# CPU_Power.net
KiCad netlist of a schematic drawn in Altium Designer
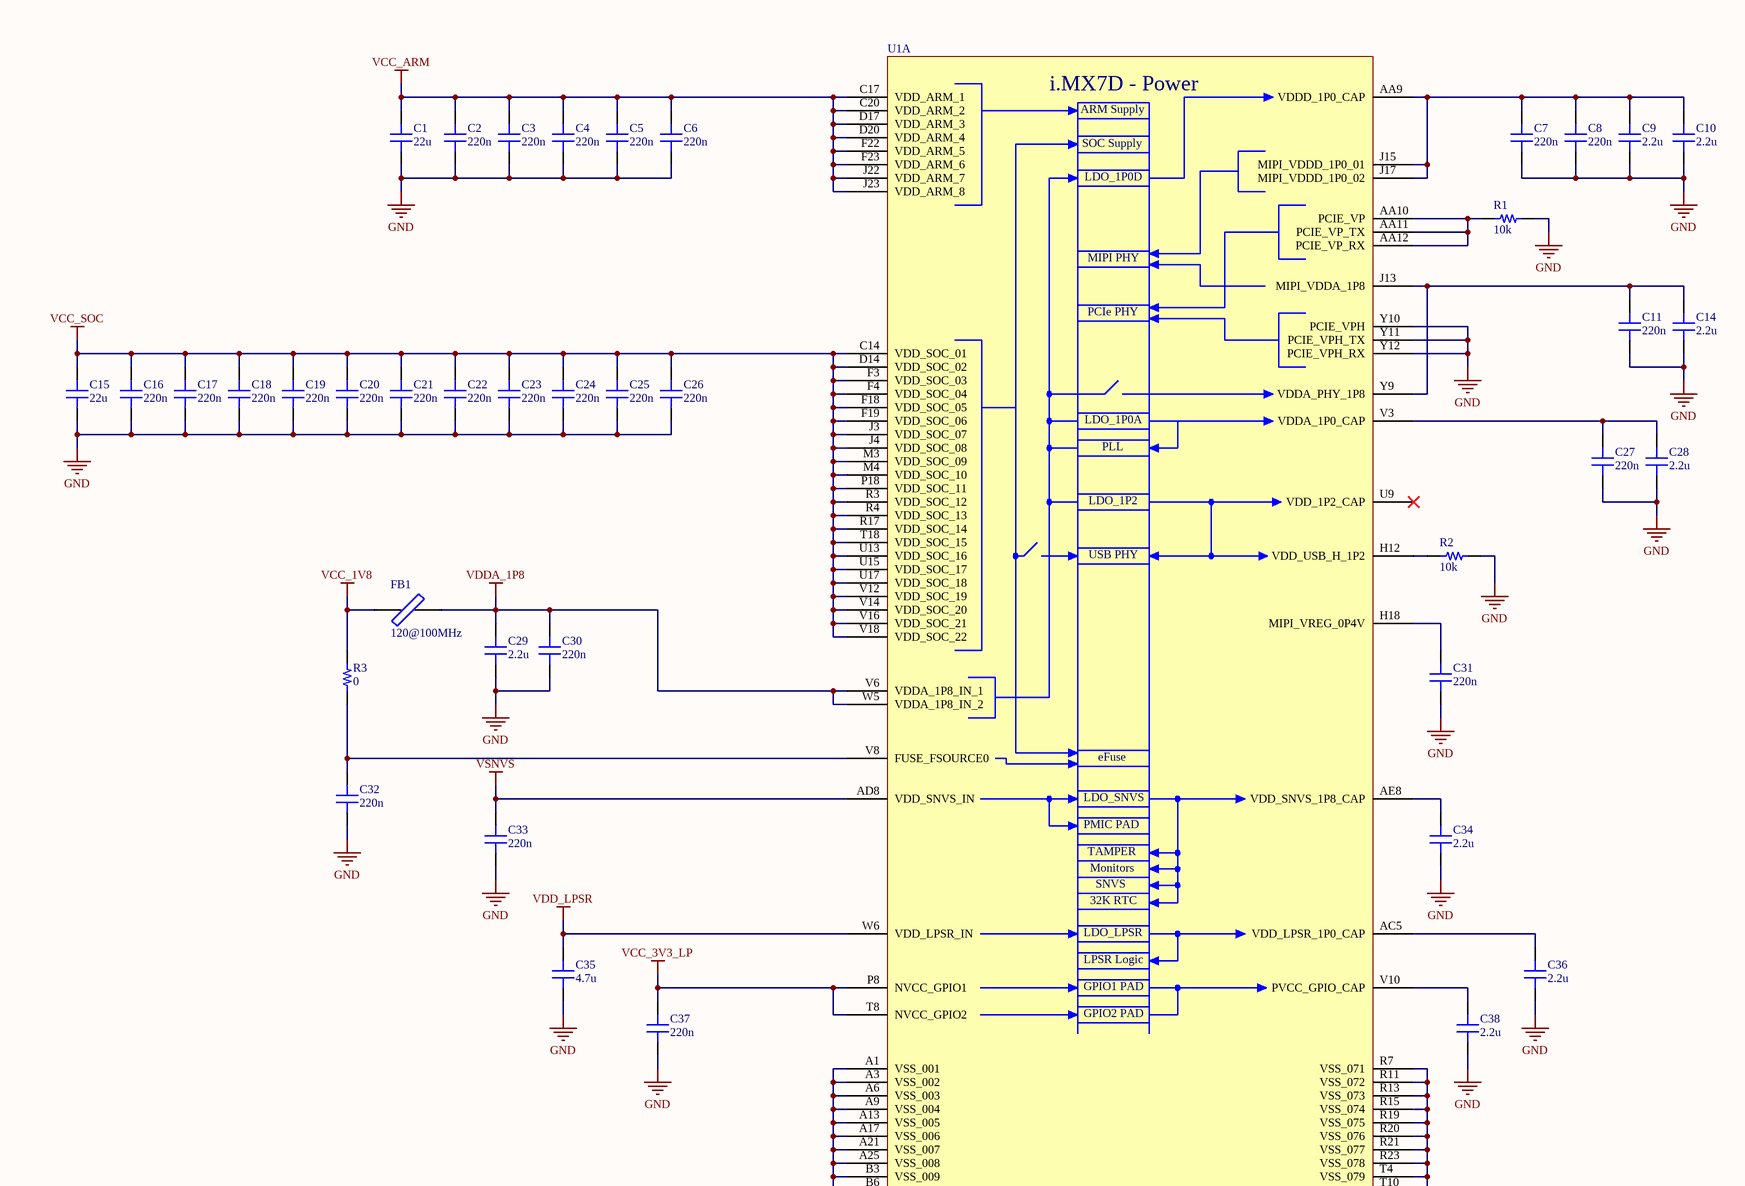
[diagram p0: CPU Power.SchDoc, top left]
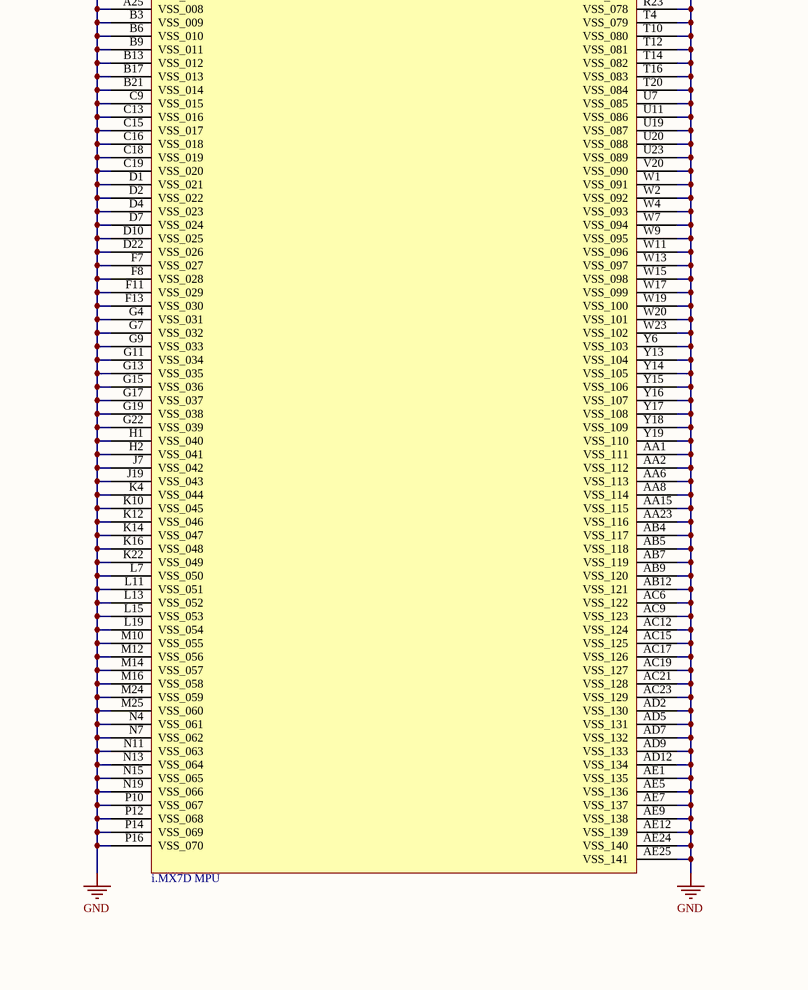
[diagram p1: CPU Power.SchDoc, bottom left]
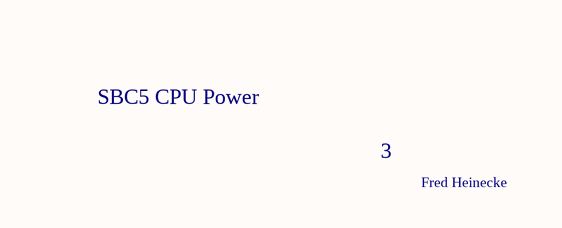
[diagram p2: CPU Power.SchDoc, bottom right]

(export (version "E")
  (design (tool "Eeschema 10.0.6"))
  (components
    (comp (ref "C1")
      (value "22u")
      (footprint "C0603")
      (description "0603 22 uF 10 V ±20% Tolerance X5R Multilayer Ceramic Chip Capacitor")
      (fields
        (field (name "MANUFACTURER") "Murata")
        (field (name "MANUFACTURER PART NUMBER") "GRM188R61A226ME15D")
      )
      (libsource (lib "SBC5") (part "GRM188R61A226ME15D"))
    )
    (comp (ref "C2")
      (value "220n")
      (footprint "C0201")
      (description "Cap Ceramic Monolithic 0.22uF 16VDC 10% SMD Paper T/R")
      (fields
        (field (name "MANUFACTURER") "Murata")
        (field (name "MANUFACTURER PART NUMBER") "GRM033R61C224KE14D")
      )
      (libsource (lib "SBC5") (part "GRM033R61C224KE14D"))
    )
    (comp (ref "C3")
      (value "220n")
      (footprint "C0201")
      (description "Cap Ceramic Monolithic 0.22uF 16VDC 10% SMD Paper T/R")
      (fields
        (field (name "MANUFACTURER") "Murata")
        (field (name "MANUFACTURER PART NUMBER") "GRM033R61C224KE14D")
      )
      (libsource (lib "SBC5") (part "GRM033R61C224KE14D"))
    )
    (comp (ref "C4")
      (value "220n")
      (footprint "C0201")
      (description "Cap Ceramic Monolithic 0.22uF 16VDC 10% SMD Paper T/R")
      (fields
        (field (name "MANUFACTURER") "Murata")
        (field (name "MANUFACTURER PART NUMBER") "GRM033R61C224KE14D")
      )
      (libsource (lib "SBC5") (part "GRM033R61C224KE14D"))
    )
    (comp (ref "C5")
      (value "220n")
      (footprint "C0201")
      (description "Cap Ceramic Monolithic 0.22uF 16VDC 10% SMD Paper T/R")
      (fields
        (field (name "MANUFACTURER") "Murata")
        (field (name "MANUFACTURER PART NUMBER") "GRM033R61C224KE14D")
      )
      (libsource (lib "SBC5") (part "GRM033R61C224KE14D"))
    )
    (comp (ref "C6")
      (value "220n")
      (footprint "C0201")
      (description "Cap Ceramic Monolithic 0.22uF 16VDC 10% SMD Paper T/R")
      (fields
        (field (name "MANUFACTURER") "Murata")
        (field (name "MANUFACTURER PART NUMBER") "GRM033R61C224KE14D")
      )
      (libsource (lib "SBC5") (part "GRM033R61C224KE14D"))
    )
    (comp (ref "C7")
      (value "220n")
      (footprint "C0201")
      (description "Cap Ceramic Monolithic 0.22uF 16VDC 10% SMD Paper T/R")
      (fields
        (field (name "MANUFACTURER") "Murata")
        (field (name "MANUFACTURER PART NUMBER") "GRM033R61C224KE14D")
      )
      (libsource (lib "SBC5") (part "GRM033R61C224KE14D"))
    )
    (comp (ref "C8")
      (value "220n")
      (footprint "C0201")
      (description "Cap Ceramic Monolithic 0.22uF 16VDC 10% SMD Paper T/R")
      (fields
        (field (name "MANUFACTURER") "Murata")
        (field (name "MANUFACTURER PART NUMBER") "GRM033R61C224KE14D")
      )
      (libsource (lib "SBC5") (part "GRM033R61C224KE14D"))
    )
    (comp (ref "C9")
      (value "2.2u")
      (footprint "C0402")
      (description "TAIYO YUDEN         LMK105BJ225MV-F            CERAMIC CAPACITOR, 2.2UF, 10V, X5R, 20%, 0402")
      (fields
        (field (name "MANUFACTURER") "Taiyo Yuden")
        (field (name "MANUFACTURER PART NUMBER") "LMK105BJ225MV-F")
      )
      (libsource (lib "SBC5") (part "LMK105BJ225MV-F"))
    )
    (comp (ref "C10")
      (value "2.2u")
      (footprint "C0402")
      (description "TAIYO YUDEN         LMK105BJ225MV-F            CERAMIC CAPACITOR, 2.2UF, 10V, X5R, 20%, 0402")
      (fields
        (field (name "MANUFACTURER") "Taiyo Yuden")
        (field (name "MANUFACTURER PART NUMBER") "LMK105BJ225MV-F")
      )
      (libsource (lib "SBC5") (part "LMK105BJ225MV-F"))
    )
    (comp (ref "C11")
      (value "220n")
      (footprint "C0201")
      (description "Cap Ceramic Monolithic 0.22uF 16VDC 10% SMD Paper T/R")
      (fields
        (field (name "MANUFACTURER") "Murata")
        (field (name "MANUFACTURER PART NUMBER") "GRM033R61C224KE14D")
      )
      (libsource (lib "SBC5") (part "GRM033R61C224KE14D"))
    )
    (comp (ref "C14")
      (value "2.2u")
      (footprint "C0402")
      (description "TAIYO YUDEN         LMK105BJ225MV-F            CERAMIC CAPACITOR, 2.2UF, 10V, X5R, 20%, 0402")
      (fields
        (field (name "MANUFACTURER") "Taiyo Yuden")
        (field (name "MANUFACTURER PART NUMBER") "LMK105BJ225MV-F")
      )
      (libsource (lib "SBC5") (part "LMK105BJ225MV-F"))
    )
    (comp (ref "C15")
      (value "22u")
      (footprint "C0603")
      (description "0603 22 uF 10 V ±20% Tolerance X5R Multilayer Ceramic Chip Capacitor")
      (fields
        (field (name "MANUFACTURER") "Murata")
        (field (name "MANUFACTURER PART NUMBER") "GRM188R61A226ME15D")
      )
      (libsource (lib "SBC5") (part "GRM188R61A226ME15D"))
    )
    (comp (ref "C16")
      (value "220n")
      (footprint "C0201")
      (description "Cap Ceramic Monolithic 0.22uF 16VDC 10% SMD Paper T/R")
      (fields
        (field (name "MANUFACTURER") "Murata")
        (field (name "MANUFACTURER PART NUMBER") "GRM033R61C224KE14D")
      )
      (libsource (lib "SBC5") (part "GRM033R61C224KE14D"))
    )
    (comp (ref "C17")
      (value "220n")
      (footprint "C0201")
      (description "Cap Ceramic Monolithic 0.22uF 16VDC 10% SMD Paper T/R")
      (fields
        (field (name "MANUFACTURER") "Murata")
        (field (name "MANUFACTURER PART NUMBER") "GRM033R61C224KE14D")
      )
      (libsource (lib "SBC5") (part "GRM033R61C224KE14D"))
    )
    (comp (ref "C18")
      (value "220n")
      (footprint "C0201")
      (description "Cap Ceramic Monolithic 0.22uF 16VDC 10% SMD Paper T/R")
      (fields
        (field (name "MANUFACTURER") "Murata")
        (field (name "MANUFACTURER PART NUMBER") "GRM033R61C224KE14D")
      )
      (libsource (lib "SBC5") (part "GRM033R61C224KE14D"))
    )
    (comp (ref "C19")
      (value "220n")
      (footprint "C0201")
      (description "Cap Ceramic Monolithic 0.22uF 16VDC 10% SMD Paper T/R")
      (fields
        (field (name "MANUFACTURER") "Murata")
        (field (name "MANUFACTURER PART NUMBER") "GRM033R61C224KE14D")
      )
      (libsource (lib "SBC5") (part "GRM033R61C224KE14D"))
    )
    (comp (ref "C20")
      (value "220n")
      (footprint "C0201")
      (description "Cap Ceramic Monolithic 0.22uF 16VDC 10% SMD Paper T/R")
      (fields
        (field (name "MANUFACTURER") "Murata")
        (field (name "MANUFACTURER PART NUMBER") "GRM033R61C224KE14D")
      )
      (libsource (lib "SBC5") (part "GRM033R61C224KE14D"))
    )
    (comp (ref "C21")
      (value "220n")
      (footprint "C0201")
      (description "Cap Ceramic Monolithic 0.22uF 16VDC 10% SMD Paper T/R")
      (fields
        (field (name "MANUFACTURER") "Murata")
        (field (name "MANUFACTURER PART NUMBER") "GRM033R61C224KE14D")
      )
      (libsource (lib "SBC5") (part "GRM033R61C224KE14D"))
    )
    (comp (ref "C22")
      (value "220n")
      (footprint "C0201")
      (description "Cap Ceramic Monolithic 0.22uF 16VDC 10% SMD Paper T/R")
      (fields
        (field (name "MANUFACTURER") "Murata")
        (field (name "MANUFACTURER PART NUMBER") "GRM033R61C224KE14D")
      )
      (libsource (lib "SBC5") (part "GRM033R61C224KE14D"))
    )
    (comp (ref "C23")
      (value "220n")
      (footprint "C0201")
      (description "Cap Ceramic Monolithic 0.22uF 16VDC 10% SMD Paper T/R")
      (fields
        (field (name "MANUFACTURER") "Murata")
        (field (name "MANUFACTURER PART NUMBER") "GRM033R61C224KE14D")
      )
      (libsource (lib "SBC5") (part "GRM033R61C224KE14D"))
    )
    (comp (ref "C24")
      (value "220n")
      (footprint "C0201")
      (description "Cap Ceramic Monolithic 0.22uF 16VDC 10% SMD Paper T/R")
      (fields
        (field (name "MANUFACTURER") "Murata")
        (field (name "MANUFACTURER PART NUMBER") "GRM033R61C224KE14D")
      )
      (libsource (lib "SBC5") (part "GRM033R61C224KE14D"))
    )
    (comp (ref "C25")
      (value "220n")
      (footprint "C0201")
      (description "Cap Ceramic Monolithic 0.22uF 16VDC 10% SMD Paper T/R")
      (fields
        (field (name "MANUFACTURER") "Murata")
        (field (name "MANUFACTURER PART NUMBER") "GRM033R61C224KE14D")
      )
      (libsource (lib "SBC5") (part "GRM033R61C224KE14D"))
    )
    (comp (ref "C26")
      (value "220n")
      (footprint "C0201")
      (description "Cap Ceramic Monolithic 0.22uF 16VDC 10% SMD Paper T/R")
      (fields
        (field (name "MANUFACTURER") "Murata")
        (field (name "MANUFACTURER PART NUMBER") "GRM033R61C224KE14D")
      )
      (libsource (lib "SBC5") (part "GRM033R61C224KE14D"))
    )
    (comp (ref "C27")
      (value "220n")
      (footprint "C0201")
      (description "Cap Ceramic Monolithic 0.22uF 16VDC 10% SMD Paper T/R")
      (fields
        (field (name "MANUFACTURER") "Murata")
        (field (name "MANUFACTURER PART NUMBER") "GRM033R61C224KE14D")
      )
      (libsource (lib "SBC5") (part "GRM033R61C224KE14D"))
    )
    (comp (ref "C28")
      (value "2.2u")
      (footprint "C0402")
      (description "TAIYO YUDEN         LMK105BJ225MV-F            CERAMIC CAPACITOR, 2.2UF, 10V, X5R, 20%, 0402")
      (fields
        (field (name "MANUFACTURER") "Taiyo Yuden")
        (field (name "MANUFACTURER PART NUMBER") "LMK105BJ225MV-F")
      )
      (libsource (lib "SBC5") (part "LMK105BJ225MV-F"))
    )
    (comp (ref "C29")
      (value "2.2u")
      (footprint "C0402")
      (description "TAIYO YUDEN         LMK105BJ225MV-F            CERAMIC CAPACITOR, 2.2UF, 10V, X5R, 20%, 0402")
      (fields
        (field (name "MANUFACTURER") "Taiyo Yuden")
        (field (name "MANUFACTURER PART NUMBER") "LMK105BJ225MV-F")
      )
      (libsource (lib "SBC5") (part "LMK105BJ225MV-F"))
    )
    (comp (ref "C30")
      (value "220n")
      (footprint "C0201")
      (description "Cap Ceramic Monolithic 0.22uF 16VDC 10% SMD Paper T/R")
      (fields
        (field (name "MANUFACTURER") "Murata")
        (field (name "MANUFACTURER PART NUMBER") "GRM033R61C224KE14D")
      )
      (libsource (lib "SBC5") (part "GRM033R61C224KE14D"))
    )
    (comp (ref "C31")
      (value "220n")
      (footprint "C0201")
      (description "Cap Ceramic Monolithic 0.22uF 16VDC 10% SMD Paper T/R")
      (fields
        (field (name "MANUFACTURER") "Murata")
        (field (name "MANUFACTURER PART NUMBER") "GRM033R61C224KE14D")
      )
      (libsource (lib "SBC5") (part "GRM033R61C224KE14D"))
    )
    (comp (ref "C32")
      (value "220n")
      (footprint "C0201")
      (description "Cap Ceramic Monolithic 0.22uF 16VDC 10% SMD Paper T/R")
      (fields
        (field (name "MANUFACTURER") "Murata")
        (field (name "MANUFACTURER PART NUMBER") "GRM033R61C224KE14D")
      )
      (libsource (lib "SBC5") (part "GRM033R61C224KE14D"))
    )
    (comp (ref "C33")
      (value "220n")
      (footprint "C0201")
      (description "Cap Ceramic Monolithic 0.22uF 16VDC 10% SMD Paper T/R")
      (fields
        (field (name "MANUFACTURER") "Murata")
        (field (name "MANUFACTURER PART NUMBER") "GRM033R61C224KE14D")
      )
      (libsource (lib "SBC5") (part "GRM033R61C224KE14D"))
    )
    (comp (ref "C34")
      (value "2.2u")
      (footprint "C0402")
      (description "TAIYO YUDEN         LMK105BJ225MV-F            CERAMIC CAPACITOR, 2.2UF, 10V, X5R, 20%, 0402")
      (fields
        (field (name "MANUFACTURER") "Taiyo Yuden")
        (field (name "MANUFACTURER PART NUMBER") "LMK105BJ225MV-F")
      )
      (libsource (lib "SBC5") (part "LMK105BJ225MV-F"))
    )
    (comp (ref "C35")
      (value "4.7u")
      (footprint "C0603")
      (description "Cap Ceramic 4.7uF 10V X5R 10% Pad SMD 0603 85C T/R")
      (fields
        (field (name "MANUFACTURER") "Samsung")
        (field (name "MANUFACTURER PART NUMBER") "CL10A475KP8NNNC")
      )
      (libsource (lib "SBC5") (part "CL10A475KP8NNNC"))
    )
    (comp (ref "C36")
      (value "2.2u")
      (footprint "C0402")
      (description "TAIYO YUDEN         LMK105BJ225MV-F            CERAMIC CAPACITOR, 2.2UF, 10V, X5R, 20%, 0402")
      (fields
        (field (name "MANUFACTURER") "Taiyo Yuden")
        (field (name "MANUFACTURER PART NUMBER") "LMK105BJ225MV-F")
      )
      (libsource (lib "SBC5") (part "LMK105BJ225MV-F"))
    )
    (comp (ref "C37")
      (value "220n")
      (footprint "C0201")
      (description "Cap Ceramic Monolithic 0.22uF 16VDC 10% SMD Paper T/R")
      (fields
        (field (name "MANUFACTURER") "Murata")
        (field (name "MANUFACTURER PART NUMBER") "GRM033R61C224KE14D")
      )
      (libsource (lib "SBC5") (part "GRM033R61C224KE14D"))
    )
    (comp (ref "C38")
      (value "2.2u")
      (footprint "C0402")
      (description "TAIYO YUDEN         LMK105BJ225MV-F            CERAMIC CAPACITOR, 2.2UF, 10V, X5R, 20%, 0402")
      (fields
        (field (name "MANUFACTURER") "Taiyo Yuden")
        (field (name "MANUFACTURER PART NUMBER") "LMK105BJ225MV-F")
      )
      (libsource (lib "SBC5") (part "LMK105BJ225MV-F"))
    )
    (comp (ref "FB1")
      (value "120@100MHz")
      (footprint "L0402")
      (fields
        (field (name "MANUFACTURER") "Murata")
        (field (name "MANUFACTURER PART NUMBER") "BLM15PD121SN1D")
        (field (name "TOLERANCE") "25%")
      )
      (libsource (lib "SBC5") (part "BLM15PD121SN1D"))
    )
    (comp (ref "R1")
      (value "10k")
      (footprint "R0201")
      (description "RES 10K OHM 1% 1/20W 0201")
      (fields
        (field (name "MANUFACTURER") "Stackpole Electronics")
        (field (name "MANUFACTURER PART NUMBER") "RMCF0201FT10K0")
      )
      (libsource (lib "SBC5") (part "RMCF0201FT10K0"))
    )
    (comp (ref "R2")
      (value "10k")
      (footprint "R0201")
      (description "RES 10K OHM 1% 1/20W 0201")
      (fields
        (field (name "MANUFACTURER") "Stackpole Electronics")
        (field (name "MANUFACTURER PART NUMBER") "RMCF0201FT10K0")
      )
      (libsource (lib "SBC5") (part "RMCF0201FT10K0"))
    )
    (comp (ref "R3")
      (value "0")
      (footprint "R0402")
      (description "RES 0 OHM JUMPER 1/16W 0402")
      (fields
        (field (name "MANUFACTURER") "Stackpole Electronics")
        (field (name "MANUFACTURER PART NUMBER") "RMCF0402ZT0R00")
      )
      (libsource (lib "SBC5") (part "RMCF0402ZT0R00"))
    )
    (comp (ref "U1")
      (value "i.MX7D MPU")
      (footprint "BGA541C75P25X25_1900X1900X140")
      (description "Heterogeneous Multicore Processing Architecture")
      (fields
        (field (name "MANUFACTURER") "NXP Freescale")
        (field (name "MANUFACTURER PART NUMBER") "MCIMX7D2DVM12SD")
      )
      (libsource (lib "SBC5") (part "MCIMX7D2DVM12SD"))
    )
  )
  (nets
    (net (code "1") (name "GND") (class "Default")
      (node (ref "C1") (pin "1") (pinfunction "1_1") (pintype "passive"))
      (node (ref "C10") (pin "1") (pinfunction "1_1") (pintype "passive"))
      (node (ref "C11") (pin "1") (pinfunction "1_1") (pintype "passive"))
      (node (ref "C14") (pin "1") (pinfunction "1_1") (pintype "passive"))
      (node (ref "C15") (pin "1") (pinfunction "1_1") (pintype "passive"))
      (node (ref "C16") (pin "1") (pinfunction "1_1") (pintype "passive"))
      (node (ref "C17") (pin "1") (pinfunction "1_1") (pintype "passive"))
      (node (ref "C18") (pin "1") (pinfunction "1_1") (pintype "passive"))
      (node (ref "C19") (pin "1") (pinfunction "1_1") (pintype "passive"))
      (node (ref "C2") (pin "1") (pinfunction "1_1") (pintype "passive"))
      (node (ref "C20") (pin "1") (pinfunction "1_1") (pintype "passive"))
      (node (ref "C21") (pin "1") (pinfunction "1_1") (pintype "passive"))
      (node (ref "C22") (pin "1") (pinfunction "1_1") (pintype "passive"))
      (node (ref "C23") (pin "1") (pinfunction "1_1") (pintype "passive"))
      (node (ref "C24") (pin "1") (pinfunction "1_1") (pintype "passive"))
      (node (ref "C25") (pin "1") (pinfunction "1_1") (pintype "passive"))
      (node (ref "C26") (pin "1") (pinfunction "1_1") (pintype "passive"))
      (node (ref "C27") (pin "1") (pinfunction "1_1") (pintype "passive"))
      (node (ref "C28") (pin "1") (pinfunction "1_1") (pintype "passive"))
      (node (ref "C29") (pin "1") (pinfunction "1_1") (pintype "passive"))
      (node (ref "C3") (pin "1") (pinfunction "1_1") (pintype "passive"))
      (node (ref "C30") (pin "1") (pinfunction "1_1") (pintype "passive"))
      (node (ref "C31") (pin "1") (pinfunction "1_1") (pintype "passive"))
      (node (ref "C32") (pin "1") (pinfunction "1_1") (pintype "passive"))
      (node (ref "C33") (pin "1") (pinfunction "1_1") (pintype "passive"))
      (node (ref "C34") (pin "1") (pinfunction "1_1") (pintype "passive"))
      (node (ref "C35") (pin "1") (pinfunction "1_1") (pintype "passive"))
      (node (ref "C36") (pin "1") (pinfunction "1_1") (pintype "passive"))
      (node (ref "C37") (pin "1") (pinfunction "1_1") (pintype "passive"))
      (node (ref "C38") (pin "1") (pinfunction "1_1") (pintype "passive"))
      (node (ref "C4") (pin "1") (pinfunction "1_1") (pintype "passive"))
      (node (ref "C5") (pin "1") (pinfunction "1_1") (pintype "passive"))
      (node (ref "C6") (pin "1") (pinfunction "1_1") (pintype "passive"))
      (node (ref "C7") (pin "1") (pinfunction "1_1") (pintype "passive"))
      (node (ref "C8") (pin "1") (pinfunction "1_1") (pintype "passive"))
      (node (ref "C9") (pin "1") (pinfunction "1_1") (pintype "passive"))
      (node (ref "R1") (pin "2") (pinfunction "2_2") (pintype "passive"))
      (node (ref "R2") (pin "2") (pinfunction "2_2") (pintype "passive"))
      (node (ref "U1") (pin "A1") (pinfunction "VSS_001_A1") (pintype "passive"))
      (node (ref "U1") (pin "A13") (pinfunction "VSS_005_A13") (pintype "passive"))
      (node (ref "U1") (pin "A17") (pinfunction "VSS_006_A17") (pintype "passive"))
      (node (ref "U1") (pin "A21") (pinfunction "VSS_007_A21") (pintype "passive"))
      (node (ref "U1") (pin "A25") (pinfunction "VSS_008_A25") (pintype "passive"))
      (node (ref "U1") (pin "A3") (pinfunction "VSS_002_A3") (pintype "passive"))
      (node (ref "U1") (pin "A6") (pinfunction "VSS_003_A6") (pintype "passive"))
      (node (ref "U1") (pin "A9") (pinfunction "VSS_004_A9") (pintype "passive"))
      (node (ref "U1") (pin "AA1") (pinfunction "VSS_111_AA1") (pintype "passive"))
      (node (ref "U1") (pin "AA15") (pinfunction "VSS_115_AA15") (pintype "passive"))
      (node (ref "U1") (pin "AA2") (pinfunction "VSS_112_AA2") (pintype "passive"))
      (node (ref "U1") (pin "AA23") (pinfunction "VSS_116_AA23") (pintype "passive"))
      (node (ref "U1") (pin "AA6") (pinfunction "VSS_113_AA6") (pintype "passive"))
      (node (ref "U1") (pin "AA8") (pinfunction "VSS_114_AA8") (pintype "passive"))
      (node (ref "U1") (pin "AB12") (pinfunction "VSS_121_AB12") (pintype "passive"))
      (node (ref "U1") (pin "AB4") (pinfunction "VSS_117_AB4") (pintype "passive"))
      (node (ref "U1") (pin "AB5") (pinfunction "VSS_118_AB5") (pintype "passive"))
      (node (ref "U1") (pin "AB7") (pinfunction "VSS_119_AB7") (pintype "passive"))
      (node (ref "U1") (pin "AB9") (pinfunction "VSS_120_AB9") (pintype "passive"))
      (node (ref "U1") (pin "AC12") (pinfunction "VSS_124_AC12") (pintype "passive"))
      (node (ref "U1") (pin "AC15") (pinfunction "VSS_125_AC15") (pintype "passive"))
      (node (ref "U1") (pin "AC17") (pinfunction "VSS_126_AC17") (pintype "passive"))
      (node (ref "U1") (pin "AC19") (pinfunction "VSS_127_AC19") (pintype "passive"))
      (node (ref "U1") (pin "AC21") (pinfunction "VSS_128_AC21") (pintype "passive"))
      (node (ref "U1") (pin "AC23") (pinfunction "VSS_129_AC23") (pintype "passive"))
      (node (ref "U1") (pin "AC6") (pinfunction "VSS_122_AC6") (pintype "passive"))
      (node (ref "U1") (pin "AC9") (pinfunction "VSS_123_AC9") (pintype "passive"))
      (node (ref "U1") (pin "AD12") (pinfunction "VSS_134_AD12") (pintype "passive"))
      (node (ref "U1") (pin "AD2") (pinfunction "VSS_130_AD2") (pintype "passive"))
      (node (ref "U1") (pin "AD5") (pinfunction "VSS_131_AD5") (pintype "passive"))
      (node (ref "U1") (pin "AD7") (pinfunction "VSS_132_AD7") (pintype "passive"))
      (node (ref "U1") (pin "AD9") (pinfunction "VSS_133_AD9") (pintype "passive"))
      (node (ref "U1") (pin "AE1") (pinfunction "VSS_135_AE1") (pintype "passive"))
      (node (ref "U1") (pin "AE12") (pinfunction "VSS_139_AE12") (pintype "passive"))
      (node (ref "U1") (pin "AE24") (pinfunction "VSS_140_AE24") (pintype "passive"))
      (node (ref "U1") (pin "AE25") (pinfunction "VSS_141_AE25") (pintype "passive"))
      (node (ref "U1") (pin "AE5") (pinfunction "VSS_136_AE5") (pintype "passive"))
      (node (ref "U1") (pin "AE7") (pinfunction "VSS_137_AE7") (pintype "passive"))
      (node (ref "U1") (pin "AE9") (pinfunction "VSS_138_AE9") (pintype "passive"))
      (node (ref "U1") (pin "B13") (pinfunction "VSS_012_B13") (pintype "passive"))
      (node (ref "U1") (pin "B17") (pinfunction "VSS_013_B17") (pintype "passive"))
      (node (ref "U1") (pin "B21") (pinfunction "VSS_014_B21") (pintype "passive"))
      (node (ref "U1") (pin "B3") (pinfunction "VSS_009_B3") (pintype "passive"))
      (node (ref "U1") (pin "B6") (pinfunction "VSS_010_B6") (pintype "passive"))
      (node (ref "U1") (pin "B9") (pinfunction "VSS_011_B9") (pintype "passive"))
      (node (ref "U1") (pin "C13") (pinfunction "VSS_016_C13") (pintype "passive"))
      (node (ref "U1") (pin "C15") (pinfunction "VSS_017_C15") (pintype "passive"))
      (node (ref "U1") (pin "C16") (pinfunction "VSS_018_C16") (pintype "passive"))
      (node (ref "U1") (pin "C18") (pinfunction "VSS_019_C18") (pintype "passive"))
      (node (ref "U1") (pin "C19") (pinfunction "VSS_020_C19") (pintype "passive"))
      (node (ref "U1") (pin "C9") (pinfunction "VSS_015_C9") (pintype "passive"))
      (node (ref "U1") (pin "D1") (pinfunction "VSS_021_D1") (pintype "passive"))
      (node (ref "U1") (pin "D10") (pinfunction "VSS_025_D10") (pintype "passive"))
      (node (ref "U1") (pin "D2") (pinfunction "VSS_022_D2") (pintype "passive"))
      (node (ref "U1") (pin "D22") (pinfunction "VSS_026_D22") (pintype "passive"))
      (node (ref "U1") (pin "D4") (pinfunction "VSS_023_D4") (pintype "passive"))
      (node (ref "U1") (pin "D7") (pinfunction "VSS_024_D7") (pintype "passive"))
      (node (ref "U1") (pin "F11") (pinfunction "VSS_029_F11") (pintype "passive"))
      (node (ref "U1") (pin "F13") (pinfunction "VSS_030_F13") (pintype "passive"))
      (node (ref "U1") (pin "F7") (pinfunction "VSS_027_F7") (pintype "passive"))
      (node (ref "U1") (pin "F8") (pinfunction "VSS_028_F8") (pintype "passive"))
      (node (ref "U1") (pin "G11") (pinfunction "VSS_034_G11") (pintype "passive"))
      (node (ref "U1") (pin "G13") (pinfunction "VSS_035_G13") (pintype "passive"))
      (node (ref "U1") (pin "G15") (pinfunction "VSS_036_G15") (pintype "passive"))
      (node (ref "U1") (pin "G17") (pinfunction "VSS_037_G17") (pintype "passive"))
      (node (ref "U1") (pin "G19") (pinfunction "VSS_038_G19") (pintype "passive"))
      (node (ref "U1") (pin "G22") (pinfunction "VSS_039_G22") (pintype "passive"))
      (node (ref "U1") (pin "G4") (pinfunction "VSS_031_G4") (pintype "passive"))
      (node (ref "U1") (pin "G7") (pinfunction "VSS_032_G7") (pintype "passive"))
      (node (ref "U1") (pin "G9") (pinfunction "VSS_033_G9") (pintype "passive"))
      (node (ref "U1") (pin "H1") (pinfunction "VSS_040_H1") (pintype "passive"))
      (node (ref "U1") (pin "H2") (pinfunction "VSS_041_H2") (pintype "passive"))
      (node (ref "U1") (pin "J19") (pinfunction "VSS_043_J19") (pintype "passive"))
      (node (ref "U1") (pin "J7") (pinfunction "VSS_042_J7") (pintype "passive"))
      (node (ref "U1") (pin "K10") (pinfunction "VSS_045_K10") (pintype "passive"))
      (node (ref "U1") (pin "K12") (pinfunction "VSS_046_K12") (pintype "passive"))
      (node (ref "U1") (pin "K14") (pinfunction "VSS_047_K14") (pintype "passive"))
      (node (ref "U1") (pin "K16") (pinfunction "VSS_048_K16") (pintype "passive"))
      (node (ref "U1") (pin "K22") (pinfunction "VSS_049_K22") (pintype "passive"))
      (node (ref "U1") (pin "K4") (pinfunction "VSS_044_K4") (pintype "passive"))
      (node (ref "U1") (pin "L11") (pinfunction "VSS_051_L11") (pintype "passive"))
      (node (ref "U1") (pin "L13") (pinfunction "VSS_052_L13") (pintype "passive"))
      (node (ref "U1") (pin "L15") (pinfunction "VSS_053_L15") (pintype "passive"))
      (node (ref "U1") (pin "L19") (pinfunction "VSS_054_L19") (pintype "passive"))
      (node (ref "U1") (pin "L7") (pinfunction "VSS_050_L7") (pintype "passive"))
      (node (ref "U1") (pin "M10") (pinfunction "VSS_055_M10") (pintype "passive"))
      (node (ref "U1") (pin "M12") (pinfunction "VSS_056_M12") (pintype "passive"))
      (node (ref "U1") (pin "M14") (pinfunction "VSS_057_M14") (pintype "passive"))
      (node (ref "U1") (pin "M16") (pinfunction "VSS_058_M16") (pintype "passive"))
      (node (ref "U1") (pin "M24") (pinfunction "VSS_059_M24") (pintype "passive"))
      (node (ref "U1") (pin "M25") (pinfunction "VSS_060_M25") (pintype "passive"))
      (node (ref "U1") (pin "N11") (pinfunction "VSS_063_N11") (pintype "passive"))
      (node (ref "U1") (pin "N13") (pinfunction "VSS_064_N13") (pintype "passive"))
      (node (ref "U1") (pin "N15") (pinfunction "VSS_065_N15") (pintype "passive"))
      (node (ref "U1") (pin "N19") (pinfunction "VSS_066_N19") (pintype "passive"))
      (node (ref "U1") (pin "N4") (pinfunction "VSS_061_N4") (pintype "passive"))
      (node (ref "U1") (pin "N7") (pinfunction "VSS_062_N7") (pintype "passive"))
      (node (ref "U1") (pin "P10") (pinfunction "VSS_067_P10") (pintype "passive"))
      (node (ref "U1") (pin "P12") (pinfunction "VSS_068_P12") (pintype "passive"))
      (node (ref "U1") (pin "P14") (pinfunction "VSS_069_P14") (pintype "passive"))
      (node (ref "U1") (pin "P16") (pinfunction "VSS_070_P16") (pintype "passive"))
      (node (ref "U1") (pin "R11") (pinfunction "VSS_072_R11") (pintype "passive"))
      (node (ref "U1") (pin "R13") (pinfunction "VSS_073_R13") (pintype "passive"))
      (node (ref "U1") (pin "R15") (pinfunction "VSS_074_R15") (pintype "passive"))
      (node (ref "U1") (pin "R19") (pinfunction "VSS_075_R19") (pintype "passive"))
      (node (ref "U1") (pin "R20") (pinfunction "VSS_076_R20") (pintype "passive"))
      (node (ref "U1") (pin "R21") (pinfunction "VSS_077_R21") (pintype "passive"))
      (node (ref "U1") (pin "R23") (pinfunction "VSS_078_R23") (pintype "passive"))
      (node (ref "U1") (pin "R7") (pinfunction "VSS_071_R7") (pintype "passive"))
      (node (ref "U1") (pin "T10") (pinfunction "VSS_080_T10") (pintype "passive"))
      (node (ref "U1") (pin "T12") (pinfunction "VSS_081_T12") (pintype "passive"))
      (node (ref "U1") (pin "T14") (pinfunction "VSS_082_T14") (pintype "passive"))
      (node (ref "U1") (pin "T16") (pinfunction "VSS_083_T16") (pintype "passive"))
      (node (ref "U1") (pin "T20") (pinfunction "VSS_084_T20") (pintype "passive"))
      (node (ref "U1") (pin "T4") (pinfunction "VSS_079_T4") (pintype "passive"))
      (node (ref "U1") (pin "U11") (pinfunction "VSS_086_U11") (pintype "passive"))
      (node (ref "U1") (pin "U19") (pinfunction "VSS_087_U19") (pintype "passive"))
      (node (ref "U1") (pin "U20") (pinfunction "VSS_088_U20") (pintype "passive"))
      (node (ref "U1") (pin "U23") (pinfunction "VSS_089_U23") (pintype "passive"))
      (node (ref "U1") (pin "U7") (pinfunction "VSS_085_U7") (pintype "passive"))
      (node (ref "U1") (pin "V20") (pinfunction "VSS_090_V20") (pintype "passive"))
      (node (ref "U1") (pin "W1") (pinfunction "VSS_091_W1") (pintype "passive"))
      (node (ref "U1") (pin "W11") (pinfunction "VSS_096_W11") (pintype "passive"))
      (node (ref "U1") (pin "W13") (pinfunction "VSS_097_W13") (pintype "passive"))
      (node (ref "U1") (pin "W15") (pinfunction "VSS_098_W15") (pintype "passive"))
      (node (ref "U1") (pin "W17") (pinfunction "VSS_099_W17") (pintype "passive"))
      (node (ref "U1") (pin "W19") (pinfunction "VSS_100_W19") (pintype "passive"))
      (node (ref "U1") (pin "W2") (pinfunction "VSS_092_W2") (pintype "passive"))
      (node (ref "U1") (pin "W20") (pinfunction "VSS_101_W20") (pintype "passive"))
      (node (ref "U1") (pin "W23") (pinfunction "VSS_102_W23") (pintype "passive"))
      (node (ref "U1") (pin "W4") (pinfunction "VSS_093_W4") (pintype "passive"))
      (node (ref "U1") (pin "W7") (pinfunction "VSS_094_W7") (pintype "passive"))
      (node (ref "U1") (pin "W9") (pinfunction "VSS_095_W9") (pintype "passive"))
      (node (ref "U1") (pin "Y10") (pinfunction "PCIE_VPH_Y10") (pintype "power_in"))
      (node (ref "U1") (pin "Y11") (pinfunction "PCIE_VPH_TX_Y11") (pintype "power_in"))
      (node (ref "U1") (pin "Y12") (pinfunction "PCIE_VPH_RX_Y12") (pintype "power_in"))
      (node (ref "U1") (pin "Y13") (pinfunction "VSS_104_Y13") (pintype "passive"))
      (node (ref "U1") (pin "Y14") (pinfunction "VSS_105_Y14") (pintype "passive"))
      (node (ref "U1") (pin "Y15") (pinfunction "VSS_106_Y15") (pintype "passive"))
      (node (ref "U1") (pin "Y16") (pinfunction "VSS_107_Y16") (pintype "passive"))
      (node (ref "U1") (pin "Y17") (pinfunction "VSS_108_Y17") (pintype "passive"))
      (node (ref "U1") (pin "Y18") (pinfunction "VSS_109_Y18") (pintype "passive"))
      (node (ref "U1") (pin "Y19") (pinfunction "VSS_110_Y19") (pintype "passive"))
      (node (ref "U1") (pin "Y6") (pinfunction "VSS_103_Y6") (pintype "passive"))
    )
    (net (code "2") (name "Net-(U1A-FUSE_FSOURCE0)") (class "Default")
      (node (ref "C32") (pin "2") (pinfunction "2_2") (pintype "passive"))
      (node (ref "R3") (pin "1") (pinfunction "1_1") (pintype "passive"))
      (node (ref "U1") (pin "V8") (pinfunction "FUSE_FSOURCE0_V8") (pintype "power_in"))
    )
    (net (code "3") (name "Net-(U1A-MIPI_VDDA_1P8)") (class "Default")
      (node (ref "C11") (pin "2") (pinfunction "2_2") (pintype "passive"))
      (node (ref "C14") (pin "2") (pinfunction "2_2") (pintype "passive"))
      (node (ref "U1") (pin "J13") (pinfunction "MIPI_VDDA_1P8_J13") (pintype "power_in"))
      (node (ref "U1") (pin "Y9") (pinfunction "VDDA_PHY_1P8_Y9") (pintype "power_in"))
    )
    (net (code "4") (name "Net-(U1A-MIPI_VDDD_1P0_01)") (class "Default")
      (node (ref "C10") (pin "2") (pinfunction "2_2") (pintype "passive"))
      (node (ref "C7") (pin "2") (pinfunction "2_2") (pintype "passive"))
      (node (ref "C8") (pin "2") (pinfunction "2_2") (pintype "passive"))
      (node (ref "C9") (pin "2") (pinfunction "2_2") (pintype "passive"))
      (node (ref "U1") (pin "AA9") (pinfunction "VDDD_1P0_CAP_AA9") (pintype "power_in"))
      (node (ref "U1") (pin "J15") (pinfunction "MIPI_VDDD_1P0_01_J15") (pintype "power_in"))
      (node (ref "U1") (pin "J17") (pinfunction "MIPI_VDDD_1P0_02_J17") (pintype "power_in"))
    )
    (net (code "5") (name "Net-(U1A-MIPI_VREG_0P4V)") (class "Default")
      (node (ref "C31") (pin "2") (pinfunction "2_2") (pintype "passive"))
      (node (ref "U1") (pin "H18") (pinfunction "MIPI_VREG_0P4V_H18") (pintype "passive"))
    )
    (net (code "6") (name "Net-(U1A-PCIE_VP)") (class "Default")
      (node (ref "R1") (pin "1") (pinfunction "1_1") (pintype "passive"))
      (node (ref "U1") (pin "AA10") (pinfunction "PCIE_VP_AA10") (pintype "power_in"))
      (node (ref "U1") (pin "AA11") (pinfunction "PCIE_VP_TX_AA11") (pintype "power_in"))
      (node (ref "U1") (pin "AA12") (pinfunction "PCIE_VP_RX_AA12") (pintype "power_in"))
    )
    (net (code "7") (name "Net-(U1A-PVCC_GPIO_CAP)") (class "Default")
      (node (ref "C38") (pin "2") (pinfunction "2_2") (pintype "passive"))
      (node (ref "U1") (pin "V10") (pinfunction "PVCC_GPIO_CAP_V10") (pintype "power_in"))
    )
    (net (code "8") (name "Net-(U1A-VDDA_1P0_CAP)") (class "Default")
      (node (ref "C27") (pin "2") (pinfunction "2_2") (pintype "passive"))
      (node (ref "C28") (pin "2") (pinfunction "2_2") (pintype "passive"))
      (node (ref "U1") (pin "V3") (pinfunction "VDDA_1P0_CAP_V3") (pintype "power_in"))
    )
    (net (code "9") (name "Net-(U1A-VDD_LPSR_1P0_CAP)") (class "Default")
      (node (ref "C36") (pin "2") (pinfunction "2_2") (pintype "passive"))
      (node (ref "U1") (pin "AC5") (pinfunction "VDD_LPSR_1P0_CAP_AC5") (pintype "power_in"))
    )
    (net (code "10") (name "Net-(U1A-VDD_SNVS_1P8_CAP)") (class "Default")
      (node (ref "C34") (pin "2") (pinfunction "2_2") (pintype "passive"))
      (node (ref "U1") (pin "AE8") (pinfunction "VDD_SNVS_1P8_CAP_AE8") (pintype "power_in"))
    )
    (net (code "11") (name "Net-(U1A-VDD_USB_H_1P2)") (class "Default")
      (node (ref "R2") (pin "1") (pinfunction "1_1") (pintype "passive"))
      (node (ref "U1") (pin "H12") (pinfunction "VDD_USB_H_1P2_H12") (pintype "power_in"))
    )
    (net (code "12") (name "VCC_1V8") (class "Default")
      (node (ref "FB1") (pin "1") (pinfunction "1_1") (pintype "passive"))
      (node (ref "R3") (pin "2") (pinfunction "2_2") (pintype "passive"))
    )
    (net (code "13") (name "VCC_3V3_LP") (class "Default")
      (node (ref "C37") (pin "2") (pinfunction "2_2") (pintype "passive"))
      (node (ref "U1") (pin "P8") (pinfunction "NVCC_GPIO1_P8") (pintype "power_in"))
      (node (ref "U1") (pin "T8") (pinfunction "NVCC_GPIO2_T8") (pintype "power_in"))
    )
    (net (code "14") (name "VCC_ARM") (class "Default")
      (node (ref "C1") (pin "2") (pinfunction "2_2") (pintype "passive"))
      (node (ref "C2") (pin "2") (pinfunction "2_2") (pintype "passive"))
      (node (ref "C3") (pin "2") (pinfunction "2_2") (pintype "passive"))
      (node (ref "C4") (pin "2") (pinfunction "2_2") (pintype "passive"))
      (node (ref "C5") (pin "2") (pinfunction "2_2") (pintype "passive"))
      (node (ref "C6") (pin "2") (pinfunction "2_2") (pintype "passive"))
      (node (ref "U1") (pin "C17") (pinfunction "VDD_ARM_1_C17") (pintype "power_in"))
      (node (ref "U1") (pin "C20") (pinfunction "VDD_ARM_2_C20") (pintype "power_in"))
      (node (ref "U1") (pin "D17") (pinfunction "VDD_ARM_3_D17") (pintype "power_in"))
      (node (ref "U1") (pin "D20") (pinfunction "VDD_ARM_4_D20") (pintype "power_in"))
      (node (ref "U1") (pin "F22") (pinfunction "VDD_ARM_5_F22") (pintype "power_in"))
      (node (ref "U1") (pin "F23") (pinfunction "VDD_ARM_6_F23") (pintype "power_in"))
      (node (ref "U1") (pin "J22") (pinfunction "VDD_ARM_7_J22") (pintype "power_in"))
      (node (ref "U1") (pin "J23") (pinfunction "VDD_ARM_8_J23") (pintype "power_in"))
    )
    (net (code "15") (name "VCC_SOC") (class "Default")
      (node (ref "C15") (pin "2") (pinfunction "2_2") (pintype "passive"))
      (node (ref "C16") (pin "2") (pinfunction "2_2") (pintype "passive"))
      (node (ref "C17") (pin "2") (pinfunction "2_2") (pintype "passive"))
      (node (ref "C18") (pin "2") (pinfunction "2_2") (pintype "passive"))
      (node (ref "C19") (pin "2") (pinfunction "2_2") (pintype "passive"))
      (node (ref "C20") (pin "2") (pinfunction "2_2") (pintype "passive"))
      (node (ref "C21") (pin "2") (pinfunction "2_2") (pintype "passive"))
      (node (ref "C22") (pin "2") (pinfunction "2_2") (pintype "passive"))
      (node (ref "C23") (pin "2") (pinfunction "2_2") (pintype "passive"))
      (node (ref "C24") (pin "2") (pinfunction "2_2") (pintype "passive"))
      (node (ref "C25") (pin "2") (pinfunction "2_2") (pintype "passive"))
      (node (ref "C26") (pin "2") (pinfunction "2_2") (pintype "passive"))
      (node (ref "U1") (pin "C14") (pinfunction "VDD_SOC_01_C14") (pintype "power_in"))
      (node (ref "U1") (pin "D14") (pinfunction "VDD_SOC_02_D14") (pintype "power_in"))
      (node (ref "U1") (pin "F18") (pinfunction "VDD_SOC_05_F18") (pintype "power_in"))
      (node (ref "U1") (pin "F19") (pinfunction "VDD_SOC_06_F19") (pintype "power_in"))
      (node (ref "U1") (pin "F3") (pinfunction "VDD_SOC_03_F3") (pintype "power_in"))
      (node (ref "U1") (pin "F4") (pinfunction "VDD_SOC_04_F4") (pintype "power_in"))
      (node (ref "U1") (pin "J3") (pinfunction "VDD_SOC_07_J3") (pintype "power_in"))
      (node (ref "U1") (pin "J4") (pinfunction "VDD_SOC_08_J4") (pintype "power_in"))
      (node (ref "U1") (pin "M3") (pinfunction "VDD_SOC_09_M3") (pintype "power_in"))
      (node (ref "U1") (pin "M4") (pinfunction "VDD_SOC_10_M4") (pintype "power_in"))
      (node (ref "U1") (pin "P18") (pinfunction "VDD_SOC_11_P18") (pintype "power_in"))
      (node (ref "U1") (pin "R17") (pinfunction "VDD_SOC_14_R17") (pintype "power_in"))
      (node (ref "U1") (pin "R3") (pinfunction "VDD_SOC_12_R3") (pintype "power_in"))
      (node (ref "U1") (pin "R4") (pinfunction "VDD_SOC_13_R4") (pintype "power_in"))
      (node (ref "U1") (pin "T18") (pinfunction "VDD_SOC_15_T18") (pintype "power_in"))
      (node (ref "U1") (pin "U13") (pinfunction "VDD_SOC_16_U13") (pintype "power_in"))
      (node (ref "U1") (pin "U15") (pinfunction "VDD_SOC_17_U15") (pintype "power_in"))
      (node (ref "U1") (pin "U17") (pinfunction "VDD_SOC_18_U17") (pintype "power_in"))
      (node (ref "U1") (pin "V12") (pinfunction "VDD_SOC_19_V12") (pintype "power_in"))
      (node (ref "U1") (pin "V14") (pinfunction "VDD_SOC_20_V14") (pintype "power_in"))
      (node (ref "U1") (pin "V16") (pinfunction "VDD_SOC_21_V16") (pintype "power_in"))
      (node (ref "U1") (pin "V18") (pinfunction "VDD_SOC_22_V18") (pintype "power_in"))
    )
    (net (code "16") (name "VDDA_1P8") (class "Default")
      (node (ref "C29") (pin "2") (pinfunction "2_2") (pintype "passive"))
      (node (ref "C30") (pin "2") (pinfunction "2_2") (pintype "passive"))
      (node (ref "FB1") (pin "2") (pinfunction "2_2") (pintype "passive"))
      (node (ref "U1") (pin "V6") (pinfunction "VDDA_1P8_IN_1_V6") (pintype "power_in"))
      (node (ref "U1") (pin "W5") (pinfunction "VDDA_1P8_IN_2_W5") (pintype "power_in"))
    )
    (net (code "17") (name "VDD_LPSR") (class "Default")
      (node (ref "C35") (pin "2") (pinfunction "2_2") (pintype "passive"))
      (node (ref "U1") (pin "W6") (pinfunction "VDD_LPSR_IN_W6") (pintype "power_in"))
    )
    (net (code "18") (name "VSNVS") (class "Default")
      (node (ref "C33") (pin "2") (pinfunction "2_2") (pintype "passive"))
      (node (ref "U1") (pin "AD8") (pinfunction "VDD_SNVS_IN_AD8") (pintype "power_in"))
    )
    (net (code "19") (name "unconnected-(U1A-VDD_1P2_CAP-PadU9)") (class "Default")
      (node (ref "U1") (pin "U9") (pinfunction "VDD_1P2_CAP_U9") (pintype "power_in+no_connect"))
    )
  )
)
